# Sheet_1.net
KiCad netlist of a schematic drawn in Altium Designer
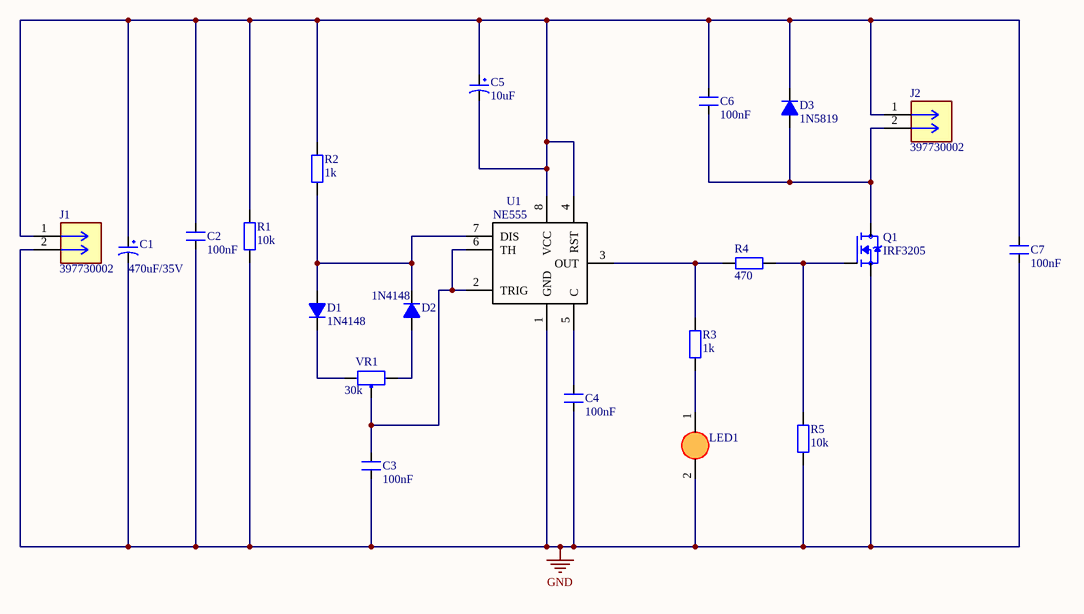
[diagram p0: Sheet_1.SchDoc]

(export (version "E")
  (design (tool "Eeschema 10.0.6"))
  (components
    (comp (ref "C1")
      (value "470uF/35V")
      (footprint "CP1.5/3.4")
      (description "Cap 100uF/35V - 470uF/16V")
      (libsource (lib "Cty1") (part "CP3"))
    )
    (comp (ref "C2")
      (value "100nF")
      (footprint "CN1.5")
      (libsource (lib "KhanhBK_SCH_Library_1") (part "CN"))
    )
    (comp (ref "C3")
      (value "100nF")
      (footprint "CN1.5")
      (libsource (lib "KhanhBK_SCH_Library_1") (part "CN"))
    )
    (comp (ref "C4")
      (value "100nF")
      (footprint "CN1.5")
      (libsource (lib "KhanhBK_SCH_Library_1") (part "CN"))
    )
    (comp (ref "C5")
      (value "10uF")
      (footprint "CP1/2")
      (description "Cap P  0,1uF < 22uF , 16 - 50V")
      (libsource (lib "Cty1") (part "CP1"))
    )
    (comp (ref "C6")
      (value "100nF")
      (footprint "CN1.5")
      (libsource (lib "KhanhBK_SCH_Library_1") (part "CN"))
    )
    (comp (ref "C7")
      (value "100nF")
      (footprint "CN1.5")
      (libsource (lib "KhanhBK_SCH_Library_1") (part "CN"))
    )
    (comp (ref "D1")
      (value "1N4148")
      (footprint "D0.5A")
      (description "D0.5A")
      (libsource (lib "Cty1") (part "D0.5A"))
    )
    (comp (ref "D2")
      (value "1N4148")
      (footprint "D0.5A")
      (description "D0.5A")
      (libsource (lib "Cty1") (part "D0.5A"))
    )
    (comp (ref "D3")
      (value "1N5819")
      (footprint "D0.5A")
      (description "D0.5A")
      (libsource (lib "Cty1") (part "D0.5A"))
    )
    (comp (ref "J1")
      (value "397730002")
      (footprint "CONN_39773-0002_MOL")
      (description "2 Position Wire to Board Terminal Block Horizontal with Board 0.100 (2.54mm) Through Hole")
      (fields (field (name "MF") "Molex"))
      (libsource (lib "397730002") (part "397730002"))
    )
    (comp (ref "J2")
      (value "397730002")
      (footprint "CONN_39773-0002_MOL")
      (description "2 Position Wire to Board Terminal Block Horizontal with Board 0.100 (2.54mm) Through Hole")
      (fields (field (name "MF") "Molex"))
      (libsource (lib "397730002") (part "397730002"))
    )
    (comp (ref "LED1")
      (value "LED5")
      (footprint "LED-5 GRe")
      (description "LED 5mm")
      (libsource (lib "Cty1") (part "LED 5mm"))
    )
    (comp (ref "Q1")
      (value "IRF3205")
      (footprint "TO254P1041X444X2933-3")
      (description "N-Channel 55V 110A (Tc) 200W (Tc) Through Hole TO-220AB")
      (fields (field (name "MF") "Infineon Technologies"))
      (libsource (lib "IRF3205_1") (part "IRF3205"))
    )
    (comp (ref "R1")
      (value "10k")
      (footprint "R1/4W")
      (description "Resistor 1/4W")
      (libsource (lib "Cty1") (part "R1/4W"))
    )
    (comp (ref "R2")
      (value "1k")
      (footprint "R1/4W")
      (description "Resistor 1/4W")
      (libsource (lib "Cty1") (part "R1/4W"))
    )
    (comp (ref "R3")
      (value "1k")
      (footprint "R1/4W")
      (description "Resistor 1/4W")
      (libsource (lib "Cty1") (part "R1/4W"))
    )
    (comp (ref "R4")
      (value "470")
      (footprint "R1/4W")
      (description "Resistor 1/4W")
      (libsource (lib "Cty1") (part "R1/4W"))
    )
    (comp (ref "R5")
      (value "10k")
      (footprint "R1/4W")
      (description "Resistor 1/4W")
      (libsource (lib "Cty1") (part "R1/4W"))
    )
    (comp (ref "U1")
      (value "NE555")
      (footprint "DIP8")
      (description "TIMER IC")
      (fields
        (field (name "MANUFACTURER PART NUMBER") "NE555DT")
        (field (name "MANUFACTURER") "STMicroelectronics")
      )
      (libsource (lib "KhanhBK_SCH_Library_1") (part "NE555"))
    )
    (comp (ref "VR1")
      (value "30k")
      (footprint "VOL_1")
      (description "Var Resistor")
      (libsource (lib "Cty1") (part "Var Resitor"))
    )
  )
  (nets
    (net (code "1") (name "GND") (class "Default")
      (node (ref "C1") (pin "2") (pinfunction "2_2") (pintype "passive"))
      (node (ref "C2") (pin "2") (pinfunction "2_2") (pintype "passive"))
      (node (ref "C3") (pin "1") (pinfunction "1_1") (pintype "passive"))
      (node (ref "C4") (pin "1") (pinfunction "1_1") (pintype "passive"))
      (node (ref "C7") (pin "2") (pinfunction "2_2") (pintype "passive"))
      (node (ref "J1") (pin "2") (pinfunction "2_2") (pintype "passive"))
      (node (ref "LED1") (pin "2") (pinfunction "K_2") (pintype "passive"))
      (node (ref "Q1") (pin "3") (pinfunction "S_3") (pintype "passive"))
      (node (ref "R1") (pin "1") (pinfunction "1_1") (pintype "passive"))
      (node (ref "R5") (pin "1") (pinfunction "1_1") (pintype "passive"))
      (node (ref "U1") (pin "1") (pinfunction "GND_1") (pintype "passive"))
    )
    (net (code "2") (name "Net-(D1-A)") (class "Default")
      (node (ref "D1") (pin "1") (pinfunction "A_1") (pintype "passive"))
      (node (ref "D2") (pin "2") (pinfunction "K_2") (pintype "passive"))
      (node (ref "R2") (pin "1") (pinfunction "1_1") (pintype "passive"))
      (node (ref "U1") (pin "7") (pinfunction "DIS_7") (pintype "passive"))
    )
    (net (code "3") (name "Net-(D1-K)") (class "Default")
      (node (ref "D1") (pin "2") (pinfunction "K_2") (pintype "passive"))
      (node (ref "VR1") (pin "3") (pinfunction "3_3") (pintype "passive"))
    )
    (net (code "4") (name "Net-(D2-A)") (class "Default")
      (node (ref "D2") (pin "1") (pinfunction "A_1") (pintype "passive"))
      (node (ref "VR1") (pin "1") (pinfunction "1_1") (pintype "passive"))
    )
    (net (code "5") (name "Net-(D3-A)") (class "Default")
      (node (ref "C6") (pin "1") (pinfunction "1_1") (pintype "passive"))
      (node (ref "D3") (pin "1") (pinfunction "A_1") (pintype "passive"))
      (node (ref "J2") (pin "2") (pinfunction "2_2") (pintype "passive"))
      (node (ref "Q1") (pin "2") (pinfunction "D_2") (pintype "passive"))
    )
    (net (code "6") (name "Net-(D3-K)") (class "Default")
      (node (ref "C1") (pin "1") (pinfunction "1_1") (pintype "passive"))
      (node (ref "C2") (pin "1") (pinfunction "1_1") (pintype "passive"))
      (node (ref "C5") (pin "1") (pinfunction "1_1") (pintype "passive"))
      (node (ref "C5") (pin "2") (pinfunction "2_2") (pintype "passive"))
      (node (ref "C6") (pin "2") (pinfunction "2_2") (pintype "passive"))
      (node (ref "C7") (pin "1") (pinfunction "1_1") (pintype "passive"))
      (node (ref "D3") (pin "2") (pinfunction "K_2") (pintype "passive"))
      (node (ref "J1") (pin "1") (pinfunction "1_1") (pintype "passive"))
      (node (ref "J2") (pin "1") (pinfunction "1_1") (pintype "passive"))
      (node (ref "R1") (pin "2") (pinfunction "2_2") (pintype "passive"))
      (node (ref "R2") (pin "2") (pinfunction "2_2") (pintype "passive"))
      (node (ref "U1") (pin "4") (pinfunction "RST_4") (pintype "passive"))
      (node (ref "U1") (pin "8") (pinfunction "VCC_8") (pintype "passive"))
    )
    (net (code "7") (name "Net-(LED1-A)") (class "Default")
      (node (ref "LED1") (pin "1") (pinfunction "A_1") (pintype "passive"))
      (node (ref "R3") (pin "1") (pinfunction "1_1") (pintype "passive"))
    )
    (net (code "8") (name "Net-(Q1-G)") (class "Default")
      (node (ref "Q1") (pin "1") (pinfunction "G_1") (pintype "passive"))
      (node (ref "R4") (pin "1") (pinfunction "1_1") (pintype "passive"))
      (node (ref "R5") (pin "2") (pinfunction "2_2") (pintype "passive"))
    )
    (net (code "9") (name "Net-(U1-C)") (class "Default")
      (node (ref "C4") (pin "2") (pinfunction "2_2") (pintype "passive"))
      (node (ref "U1") (pin "5") (pinfunction "C_5") (pintype "passive"))
    )
    (net (code "10") (name "Net-(U1-OUT)") (class "Default")
      (node (ref "R3") (pin "2") (pinfunction "2_2") (pintype "passive"))
      (node (ref "R4") (pin "2") (pinfunction "2_2") (pintype "passive"))
      (node (ref "U1") (pin "3") (pinfunction "OUT_3") (pintype "passive"))
    )
    (net (code "11") (name "Net-(U1-TH)") (class "Default")
      (node (ref "C3") (pin "2") (pinfunction "2_2") (pintype "passive"))
      (node (ref "U1") (pin "2") (pinfunction "TRIG_2") (pintype "passive"))
      (node (ref "U1") (pin "6") (pinfunction "TH_6") (pintype "passive"))
      (node (ref "VR1") (pin "2") (pinfunction "2_2") (pintype "passive"))
    )
  )
)
